# adapterSchematic.net
KiCad netlist of a schematic drawn in EAGLE
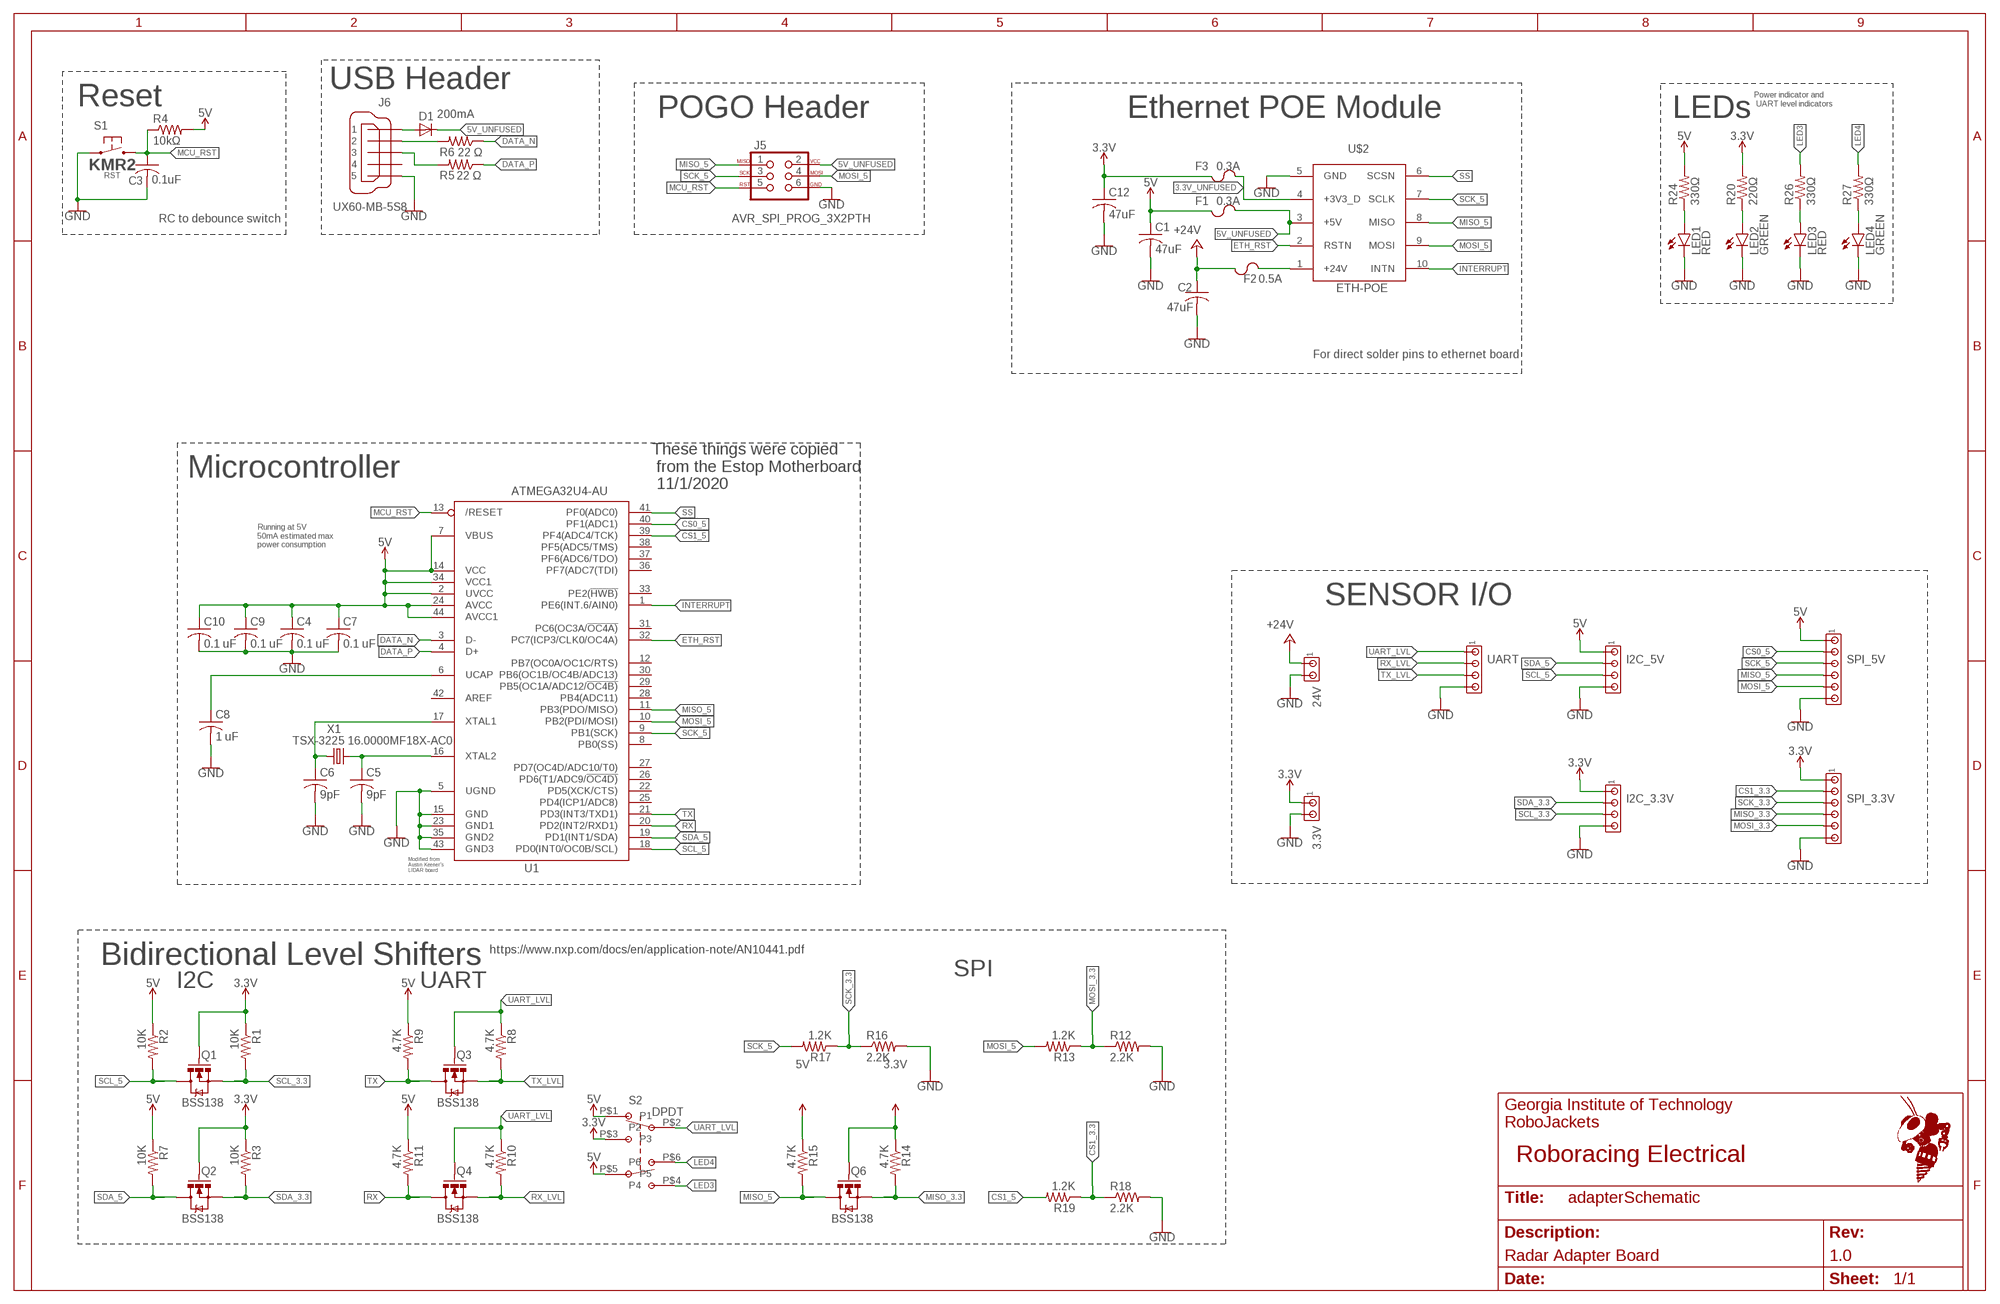
[diagram p0: schematic, sheet 1]

(export (version "E")
  (design (tool "Eeschema 10.0.6"))
  (components
    (comp (ref "3.3V")
      (value "MTA02-100")
      (footprint "eagle-import:10X02MTA")
      (libsource (lib "eagle-import") (part "MTA02-100"))
    )
    (comp (ref "24V")
      (value "MTA02-100")
      (footprint "eagle-import:10X02MTA")
      (libsource (lib "eagle-import") (part "MTA02-100"))
    )
    (comp (ref "C1")
      (value "47uF")
      (footprint "eagle-import:C1206")
      (libsource (lib "eagle-import") (part "C-USC1206"))
    )
    (comp (ref "C2")
      (value "47uF")
      (footprint "eagle-import:C1206")
      (libsource (lib "eagle-import") (part "C-USC1206"))
    )
    (comp (ref "C3")
      (value "0.1uF")
      (footprint "eagle-import:C0603")
      (libsource (lib "eagle-import") (part "C-USC0603"))
    )
    (comp (ref "C4")
      (value "0.1 uF")
      (footprint "eagle-import:C0603")
      (libsource (lib "eagle-import") (part "resistor_348_C-USC0603"))
    )
    (comp (ref "C5")
      (value "9pF")
      (footprint "eagle-import:C0603")
      (libsource (lib "eagle-import") (part "resistor_348_C-USC0603"))
    )
    (comp (ref "C6")
      (value "9pF")
      (footprint "eagle-import:C0603")
      (libsource (lib "eagle-import") (part "resistor_348_C-USC0603"))
    )
    (comp (ref "C7")
      (value "0.1 uF")
      (footprint "eagle-import:C0603")
      (libsource (lib "eagle-import") (part "resistor_348_C-USC0603"))
    )
    (comp (ref "C8")
      (value "1 uF")
      (footprint "eagle-import:C0603")
      (libsource (lib "eagle-import") (part "resistor_348_C-USC0603"))
    )
    (comp (ref "C9")
      (value "0.1 uF")
      (footprint "eagle-import:C0603")
      (libsource (lib "eagle-import") (part "resistor_348_C-USC0603"))
    )
    (comp (ref "C10")
      (value "0.1 uF")
      (footprint "eagle-import:C0603")
      (libsource (lib "eagle-import") (part "resistor_348_C-USC0603"))
    )
    (comp (ref "C12")
      (value "47uF")
      (footprint "eagle-import:C1206")
      (libsource (lib "eagle-import") (part "C-USC1206"))
    )
    (comp (ref "D1")
      (value "200mA")
      (footprint "eagle-import:SOD323-R")
      (libsource (lib "eagle-import") (part "DIODE-SOD323-R"))
    )
    (comp (ref "F1")
      (value "0.3A")
      (footprint "eagle-import:F1206")
      (libsource (lib "eagle-import") (part "CHIP_FUSE1206"))
    )
    (comp (ref "F2")
      (value "0.5A")
      (footprint "eagle-import:F1206")
      (libsource (lib "eagle-import") (part "CHIP_FUSE1206"))
    )
    (comp (ref "F3")
      (value "0.3A")
      (footprint "eagle-import:F1206")
      (libsource (lib "eagle-import") (part "CHIP_FUSE1206"))
    )
    (comp (ref "I2C_3.3V")
      (value "MTA04-100")
      (footprint "eagle-import:10X04MTA")
      (libsource (lib "eagle-import") (part "MTA04-100"))
    )
    (comp (ref "I2C_5V")
      (value "MTA04-100")
      (footprint "eagle-import:10X04MTA")
      (libsource (lib "eagle-import") (part "MTA04-100"))
    )
    (comp (ref "J5")
      (value "AVR_SPI_PROG_3X2PTH")
      (footprint "eagle-import:2X3")
      (libsource (lib "eagle-import") (part "AVR_SPI_PROG_3X2PTH"))
    )
    (comp (ref "J6")
      (value "UX60-MB-5S8")
      (footprint "eagle-import:UX60-MB-5S8")
      (libsource (lib "eagle-import") (part "UX60-MB-5S?8"))
    )
    (comp (ref "LED1")
      (value "RED")
      (footprint "eagle-import:CHIP-LED0603")
      (libsource (lib "eagle-import") (part "LEDCHIP-LED0603"))
    )
    (comp (ref "LED2")
      (value "GREEN")
      (footprint "eagle-import:CHIP-LED0603")
      (libsource (lib "eagle-import") (part "LEDCHIP-LED0603"))
    )
    (comp (ref "LED3")
      (value "RED")
      (footprint "eagle-import:CHIP-LED0603")
      (libsource (lib "eagle-import") (part "LEDCHIP-LED0603"))
    )
    (comp (ref "LED4")
      (value "GREEN")
      (footprint "eagle-import:CHIP-LED0603")
      (libsource (lib "eagle-import") (part "LEDCHIP-LED0603"))
    )
    (comp (ref "Q1")
      (value "BSS138")
      (footprint "eagle-import:SOT23-3")
      (libsource (lib "eagle-import") (part "MOSFET-NCHANNELSMD"))
    )
    (comp (ref "Q2")
      (value "BSS138")
      (footprint "eagle-import:SOT23-3")
      (libsource (lib "eagle-import") (part "MOSFET-NCHANNELSMD"))
    )
    (comp (ref "Q3")
      (value "BSS138")
      (footprint "eagle-import:SOT23-3")
      (libsource (lib "eagle-import") (part "MOSFET-NCHANNELSMD"))
    )
    (comp (ref "Q4")
      (value "BSS138")
      (footprint "eagle-import:SOT23-3")
      (libsource (lib "eagle-import") (part "MOSFET-NCHANNELSMD"))
    )
    (comp (ref "Q6")
      (value "BSS138")
      (footprint "eagle-import:SOT23-3")
      (libsource (lib "eagle-import") (part "MOSFET-NCHANNELSMD"))
    )
    (comp (ref "R1")
      (value "10K")
      (footprint "eagle-import:0603-RES")
      (libsource (lib "eagle-import") (part "RESISTOR0603-RES"))
    )
    (comp (ref "R2")
      (value "10K")
      (footprint "eagle-import:0603-RES")
      (libsource (lib "eagle-import") (part "RESISTOR0603-RES"))
    )
    (comp (ref "R3")
      (value "10K")
      (footprint "eagle-import:0603-RES")
      (libsource (lib "eagle-import") (part "RESISTOR0603-RES"))
    )
    (comp (ref "R4")
      (value "10kΩ")
      (footprint "eagle-import:R0603")
      (libsource (lib "eagle-import") (part "R-US_R0603"))
    )
    (comp (ref "R5")
      (value "22 Ω")
      (footprint "eagle-import:R0603")
      (libsource (lib "eagle-import") (part "R-US_R0603"))
    )
    (comp (ref "R6")
      (value "22 Ω")
      (footprint "eagle-import:R0603")
      (libsource (lib "eagle-import") (part "R-US_R0603"))
    )
    (comp (ref "R7")
      (value "10K")
      (footprint "eagle-import:0603-RES")
      (libsource (lib "eagle-import") (part "RESISTOR0603-RES"))
    )
    (comp (ref "R8")
      (value "4.7K")
      (footprint "eagle-import:0603-RES")
      (libsource (lib "eagle-import") (part "RESISTOR0603-RES"))
    )
    (comp (ref "R9")
      (value "4.7K")
      (footprint "eagle-import:0603-RES")
      (libsource (lib "eagle-import") (part "RESISTOR0603-RES"))
    )
    (comp (ref "R10")
      (value "4.7K")
      (footprint "eagle-import:0603-RES")
      (libsource (lib "eagle-import") (part "RESISTOR0603-RES"))
    )
    (comp (ref "R11")
      (value "4.7K")
      (footprint "eagle-import:0603-RES")
      (libsource (lib "eagle-import") (part "RESISTOR0603-RES"))
    )
    (comp (ref "R12")
      (value "2.2K")
      (footprint "eagle-import:0603-RES")
      (libsource (lib "eagle-import") (part "RESISTOR0603-RES"))
    )
    (comp (ref "R13")
      (value "1.2K")
      (footprint "eagle-import:0603-RES")
      (libsource (lib "eagle-import") (part "RESISTOR0603-RES"))
    )
    (comp (ref "R14")
      (value "4.7K")
      (footprint "eagle-import:0603-RES")
      (libsource (lib "eagle-import") (part "RESISTOR0603-RES"))
    )
    (comp (ref "R15")
      (value "4.7K")
      (footprint "eagle-import:0603-RES")
      (libsource (lib "eagle-import") (part "RESISTOR0603-RES"))
    )
    (comp (ref "R16")
      (value "2.2K")
      (footprint "eagle-import:0603-RES")
      (libsource (lib "eagle-import") (part "RESISTOR0603-RES"))
    )
    (comp (ref "R17")
      (value "1.2K")
      (footprint "eagle-import:0603-RES")
      (libsource (lib "eagle-import") (part "RESISTOR0603-RES"))
    )
    (comp (ref "R18")
      (value "2.2K")
      (footprint "eagle-import:0603-RES")
      (libsource (lib "eagle-import") (part "RESISTOR0603-RES"))
    )
    (comp (ref "R19")
      (value "1.2K")
      (footprint "eagle-import:0603-RES")
      (libsource (lib "eagle-import") (part "RESISTOR0603-RES"))
    )
    (comp (ref "R20")
      (value "220Ω")
      (footprint "eagle-import:R0603")
      (libsource (lib "eagle-import") (part "R-US_R0603"))
    )
    (comp (ref "R24")
      (value "330Ω")
      (footprint "eagle-import:R0603")
      (libsource (lib "eagle-import") (part "R-US_R0603"))
    )
    (comp (ref "R26")
      (value "330Ω")
      (footprint "eagle-import:R0603")
      (libsource (lib "eagle-import") (part "R-US_R0603"))
    )
    (comp (ref "R27")
      (value "330Ω")
      (footprint "eagle-import:R0603")
      (libsource (lib "eagle-import") (part "R-US_R0603"))
    )
    (comp (ref "S1")
      (value "KMR2")
      (footprint "eagle-import:KMR2")
      (fields (field (name "FUNCTION") "Reset") (field (name "FUNCTION_1") "RST"))
      (libsource (lib "eagle-import") (part "KMR2"))
    )
    (comp (ref "SPI_3.3V")
      (value "MTA06-100")
      (footprint "eagle-import:10X06MTA")
      (libsource (lib "eagle-import") (part "MTA06-100"))
    )
    (comp (ref "SPI_5V")
      (value "MTA06-100")
      (footprint "eagle-import:10X06MTA")
      (libsource (lib "eagle-import") (part "MTA06-100"))
    )
    (comp (ref "U$2")
      (value "ETH-POE")
      (footprint "eagle-import:HDRVR10W64P4000X254_2X5_1016X508X254B")
      (libsource (lib "eagle-import") (part "ETH-POE"))
    )
    (comp (ref "U$4")
      (value "DPDT_SLIDE_SWITCH")
      (footprint "eagle-import:DPDT_SLIDE_SWITCH")
      (libsource (lib "eagle-import") (part "DPDT_SLIDE_SWITCH"))
    )
    (comp (ref "U1")
      (value "ATMEGA32U4-AU")
      (footprint "eagle-import:TQFP44")
      (libsource (lib "eagle-import") (part "ATMEGA32U4-AU"))
    )
    (comp (ref "UART")
      (value "MTA04-100")
      (footprint "eagle-import:10X04MTA")
      (libsource (lib "eagle-import") (part "MTA04-100"))
    )
    (comp (ref "X1")
      (value "TSX-3225 16.0000MF18X-AC0")
      (footprint "eagle-import:XTAL-3.2X2.5")
      (libsource (lib "eagle-import") (part "XTAL-3.2X2.5"))
    )
  )
  (nets
    (net (code "1") (name "+24V") (class "Default")
      (node (ref "24V") (pin "1") (pinfunction "1_1") (pintype "passive"))
      (node (ref "C2") (pin "1") (pinfunction "1_1") (pintype "passive"))
      (node (ref "F2") (pin "1") (pinfunction "1_1") (pintype "bidirectional"))
    )
    (net (code "2") (name "3.3V") (class "Default")
      (node (ref "3.3V") (pin "1") (pinfunction "1_1") (pintype "passive"))
      (node (ref "C12") (pin "1") (pinfunction "1_1") (pintype "passive"))
      (node (ref "F3") (pin "1") (pinfunction "1_1") (pintype "bidirectional"))
      (node (ref "I2C_3.3V") (pin "1") (pinfunction "1_1") (pintype "passive"))
      (node (ref "Q1") (pin "1") (pinfunction "G_1") (pintype "passive"))
      (node (ref "Q2") (pin "1") (pinfunction "G_1") (pintype "passive"))
      (node (ref "Q6") (pin "1") (pinfunction "G_1") (pintype "passive"))
      (node (ref "R1") (pin "1") (pinfunction "1_1") (pintype "passive"))
      (node (ref "R14") (pin "1") (pinfunction "1_1") (pintype "passive"))
      (node (ref "R20") (pin "2") (pinfunction "2_2") (pintype "passive"))
      (node (ref "R3") (pin "1") (pinfunction "1_1") (pintype "passive"))
      (node (ref "SPI_3.3V") (pin "1") (pinfunction "1_1") (pintype "passive"))
      (node (ref "U$4") (pin "P$3") (pinfunction "P3_P$3") (pintype "bidirectional"))
    )
    (net (code "3") (name "3.3V_UNFUSED") (class "Default")
      (node (ref "F3") (pin "2") (pinfunction "2_2") (pintype "bidirectional"))
      (node (ref "U$2") (pin "4") (pinfunction "+3V3_D_4") (pintype "bidirectional"))
    )
    (net (code "4") (name "5V") (class "Default")
      (node (ref "C1") (pin "1") (pinfunction "1_1") (pintype "passive"))
      (node (ref "C10") (pin "1") (pinfunction "1_1") (pintype "passive"))
      (node (ref "C4") (pin "1") (pinfunction "1_1") (pintype "passive"))
      (node (ref "C7") (pin "1") (pinfunction "1_1") (pintype "passive"))
      (node (ref "C9") (pin "1") (pinfunction "1_1") (pintype "passive"))
      (node (ref "F1") (pin "1") (pinfunction "1_1") (pintype "bidirectional"))
      (node (ref "I2C_5V") (pin "1") (pinfunction "1_1") (pintype "passive"))
      (node (ref "R11") (pin "1") (pinfunction "1_1") (pintype "passive"))
      (node (ref "R15") (pin "1") (pinfunction "1_1") (pintype "passive"))
      (node (ref "R2") (pin "1") (pinfunction "1_1") (pintype "passive"))
      (node (ref "R24") (pin "2") (pinfunction "2_2") (pintype "passive"))
      (node (ref "R4") (pin "2") (pinfunction "2_2") (pintype "passive"))
      (node (ref "R7") (pin "1") (pinfunction "1_1") (pintype "passive"))
      (node (ref "R9") (pin "1") (pinfunction "1_1") (pintype "passive"))
      (node (ref "SPI_5V") (pin "1") (pinfunction "1_1") (pintype "passive"))
      (node (ref "U$4") (pin "P$1") (pinfunction "P1_P$1") (pintype "bidirectional"))
      (node (ref "U$4") (pin "P$5") (pinfunction "P5_P$5") (pintype "bidirectional"))
      (node (ref "U1") (pin "14") (pinfunction "VCC_14") (pintype "bidirectional"))
      (node (ref "U1") (pin "2") (pinfunction "UVCC_2") (pintype "bidirectional"))
      (node (ref "U1") (pin "24") (pinfunction "AVCC_24") (pintype "bidirectional"))
      (node (ref "U1") (pin "34") (pinfunction "VCC1_34") (pintype "bidirectional"))
      (node (ref "U1") (pin "44") (pinfunction "AVCC1_44") (pintype "bidirectional"))
      (node (ref "U1") (pin "7") (pinfunction "VBUS_7") (pintype "bidirectional"))
    )
    (net (code "5") (name "5V_UNFUSED") (class "Default")
      (node (ref "D1") (pin "C") (pinfunction "C_C") (pintype "passive"))
      (node (ref "F1") (pin "2") (pinfunction "2_2") (pintype "bidirectional"))
      (node (ref "J5") (pin "2") (pinfunction "2_2") (pintype "passive"))
      (node (ref "U$2") (pin "3") (pinfunction "+5V_3") (pintype "bidirectional"))
    )
    (net (code "6") (name "CS0_5") (class "Default")
      (node (ref "SPI_5V") (pin "2") (pinfunction "2_2") (pintype "passive"))
      (node (ref "U1") (pin "40") (pinfunction "PF1(ADC1)_40") (pintype "bidirectional"))
    )
    (net (code "7") (name "CS1_3.3") (class "Default")
      (node (ref "R18") (pin "1") (pinfunction "1_1") (pintype "passive"))
      (node (ref "R19") (pin "1") (pinfunction "1_1") (pintype "passive"))
      (node (ref "SPI_3.3V") (pin "2") (pinfunction "2_2") (pintype "passive"))
    )
    (net (code "8") (name "CS1_5") (class "Default")
      (node (ref "R19") (pin "2") (pinfunction "2_2") (pintype "passive"))
      (node (ref "U1") (pin "39") (pinfunction "PF4(ADC4/TCK)_39") (pintype "bidirectional"))
    )
    (net (code "9") (name "DATA_N") (class "Default")
      (node (ref "R6") (pin "1") (pinfunction "1_1") (pintype "passive"))
      (node (ref "U1") (pin "3") (pinfunction "D-_3") (pintype "bidirectional"))
    )
    (net (code "10") (name "DATA_P") (class "Default")
      (node (ref "R5") (pin "1") (pinfunction "1_1") (pintype "passive"))
      (node (ref "U1") (pin "4") (pinfunction "D+_4") (pintype "bidirectional"))
    )
    (net (code "11") (name "ETH_RST") (class "Default")
      (node (ref "U$2") (pin "2") (pinfunction "RSTN_2") (pintype "bidirectional"))
      (node (ref "U1") (pin "32") (pinfunction "PC7(ICP3/CLK0/OC4A)_32") (pintype "bidirectional"))
    )
    (net (code "12") (name "GND") (class "Default")
      (node (ref "24V") (pin "2") (pinfunction "2_2") (pintype "passive"))
      (node (ref "3.3V") (pin "2") (pinfunction "2_2") (pintype "passive"))
      (node (ref "C1") (pin "2") (pinfunction "2_2") (pintype "passive"))
      (node (ref "C10") (pin "2") (pinfunction "2_2") (pintype "passive"))
      (node (ref "C12") (pin "2") (pinfunction "2_2") (pintype "passive"))
      (node (ref "C2") (pin "2") (pinfunction "2_2") (pintype "passive"))
      (node (ref "C3") (pin "2") (pinfunction "2_2") (pintype "passive"))
      (node (ref "C4") (pin "2") (pinfunction "2_2") (pintype "passive"))
      (node (ref "C5") (pin "2") (pinfunction "2_2") (pintype "passive"))
      (node (ref "C6") (pin "2") (pinfunction "2_2") (pintype "passive"))
      (node (ref "C7") (pin "2") (pinfunction "2_2") (pintype "passive"))
      (node (ref "C8") (pin "2") (pinfunction "2_2") (pintype "passive"))
      (node (ref "C9") (pin "2") (pinfunction "2_2") (pintype "passive"))
      (node (ref "I2C_3.3V") (pin "4") (pinfunction "4_4") (pintype "passive"))
      (node (ref "I2C_5V") (pin "4") (pinfunction "4_4") (pintype "passive"))
      (node (ref "J5") (pin "6") (pinfunction "6_6") (pintype "passive"))
      (node (ref "J6") (pin "5") (pinfunction "5_5") (pintype "passive"))
      (node (ref "LED1") (pin "C") (pinfunction "C_C") (pintype "passive"))
      (node (ref "LED2") (pin "C") (pinfunction "C_C") (pintype "passive"))
      (node (ref "LED3") (pin "C") (pinfunction "C_C") (pintype "passive"))
      (node (ref "LED4") (pin "C") (pinfunction "C_C") (pintype "passive"))
      (node (ref "R12") (pin "2") (pinfunction "2_2") (pintype "passive"))
      (node (ref "R16") (pin "2") (pinfunction "2_2") (pintype "passive"))
      (node (ref "R18") (pin "2") (pinfunction "2_2") (pintype "passive"))
      (node (ref "S1") (pin "1.1") (pinfunction "1_1.1") (pintype "passive"))
      (node (ref "S1") (pin "1.2") (pinfunction "1_1.2") (pintype "passive"))
      (node (ref "SPI_3.3V") (pin "6") (pinfunction "6_6") (pintype "passive"))
      (node (ref "SPI_5V") (pin "6") (pinfunction "6_6") (pintype "passive"))
      (node (ref "U$2") (pin "5") (pinfunction "GND_5") (pintype "bidirectional"))
      (node (ref "U1") (pin "15") (pinfunction "GND_15") (pintype "bidirectional"))
      (node (ref "U1") (pin "23") (pinfunction "GND1_23") (pintype "bidirectional"))
      (node (ref "U1") (pin "35") (pinfunction "GND2_35") (pintype "bidirectional"))
      (node (ref "U1") (pin "43") (pinfunction "GND3_43") (pintype "bidirectional"))
      (node (ref "U1") (pin "5") (pinfunction "UGND_5") (pintype "bidirectional"))
      (node (ref "UART") (pin "4") (pinfunction "4_4") (pintype "passive"))
    )
    (net (code "13") (name "INTERRUPT") (class "Default")
      (node (ref "U$2") (pin "10") (pinfunction "INTN_10") (pintype "bidirectional"))
      (node (ref "U1") (pin "1") (pinfunction "PE6(INT.6/AIN0)_1") (pintype "bidirectional"))
    )
    (net (code "14") (name "LED3") (class "Default")
      (node (ref "R26") (pin "2") (pinfunction "2_2") (pintype "passive"))
      (node (ref "U$4") (pin "P$4") (pinfunction "P4_P$4") (pintype "bidirectional"))
    )
    (net (code "15") (name "LED4") (class "Default")
      (node (ref "R27") (pin "2") (pinfunction "2_2") (pintype "passive"))
      (node (ref "U$4") (pin "P$6") (pinfunction "P6_P$6") (pintype "bidirectional"))
    )
    (net (code "16") (name "MCU_RST") (class "Default")
      (node (ref "C3") (pin "1") (pinfunction "1_1") (pintype "passive"))
      (node (ref "J5") (pin "5") (pinfunction "5_5") (pintype "passive"))
      (node (ref "R4") (pin "1") (pinfunction "1_1") (pintype "passive"))
      (node (ref "S1") (pin "2.1") (pinfunction "2_2.1") (pintype "passive"))
      (node (ref "S1") (pin "2.2") (pinfunction "2_2.2") (pintype "passive"))
      (node (ref "U1") (pin "13") (pinfunction "/RESET_13") (pintype "bidirectional"))
    )
    (net (code "17") (name "MISO_3.3") (class "Default")
      (node (ref "Q6") (pin "2") (pinfunction "S_2") (pintype "passive"))
      (node (ref "R14") (pin "2") (pinfunction "2_2") (pintype "passive"))
      (node (ref "SPI_3.3V") (pin "4") (pinfunction "4_4") (pintype "passive"))
    )
    (net (code "18") (name "MISO_5") (class "Default")
      (node (ref "J5") (pin "1") (pinfunction "1_1") (pintype "passive"))
      (node (ref "Q6") (pin "3") (pinfunction "D_3") (pintype "passive"))
      (node (ref "R15") (pin "2") (pinfunction "2_2") (pintype "passive"))
      (node (ref "SPI_5V") (pin "4") (pinfunction "4_4") (pintype "passive"))
      (node (ref "U$2") (pin "8") (pinfunction "MISO_8") (pintype "bidirectional"))
      (node (ref "U1") (pin "11") (pinfunction "PB3(PDO/MISO)_11") (pintype "bidirectional"))
    )
    (net (code "19") (name "MOSI_3.3") (class "Default")
      (node (ref "R12") (pin "1") (pinfunction "1_1") (pintype "passive"))
      (node (ref "R13") (pin "1") (pinfunction "1_1") (pintype "passive"))
      (node (ref "SPI_3.3V") (pin "5") (pinfunction "5_5") (pintype "passive"))
    )
    (net (code "20") (name "MOSI_5") (class "Default")
      (node (ref "J5") (pin "4") (pinfunction "4_4") (pintype "passive"))
      (node (ref "R13") (pin "2") (pinfunction "2_2") (pintype "passive"))
      (node (ref "SPI_5V") (pin "5") (pinfunction "5_5") (pintype "passive"))
      (node (ref "U$2") (pin "9") (pinfunction "MOSI_9") (pintype "bidirectional"))
      (node (ref "U1") (pin "10") (pinfunction "PB2(PDI/MOSI)_10") (pintype "bidirectional"))
    )
    (net (code "21") (name "Net-(D1-PadA)") (class "Default")
      (node (ref "D1") (pin "A") (pinfunction "A_A") (pintype "passive"))
      (node (ref "J6") (pin "1") (pinfunction "1_1") (pintype "passive"))
    )
    (net (code "22") (name "Net-(J6-Pad2)") (class "Default")
      (node (ref "J6") (pin "2") (pinfunction "2_2") (pintype "passive"))
      (node (ref "R6") (pin "2") (pinfunction "2_2") (pintype "passive"))
    )
    (net (code "23") (name "Net-(J6-Pad3)") (class "Default")
      (node (ref "J6") (pin "3") (pinfunction "3_3") (pintype "passive"))
      (node (ref "R5") (pin "2") (pinfunction "2_2") (pintype "passive"))
    )
    (net (code "24") (name "Net-(LED1-PadA)") (class "Default")
      (node (ref "LED1") (pin "A") (pinfunction "A_A") (pintype "passive"))
      (node (ref "R24") (pin "1") (pinfunction "1_1") (pintype "passive"))
    )
    (net (code "25") (name "Net-(LED2-PadA)") (class "Default")
      (node (ref "LED2") (pin "A") (pinfunction "A_A") (pintype "passive"))
      (node (ref "R20") (pin "1") (pinfunction "1_1") (pintype "passive"))
    )
    (net (code "26") (name "Net-(LED3-PadA)") (class "Default")
      (node (ref "LED3") (pin "A") (pinfunction "A_A") (pintype "passive"))
      (node (ref "R26") (pin "1") (pinfunction "1_1") (pintype "passive"))
    )
    (net (code "27") (name "Net-(LED4-PadA)") (class "Default")
      (node (ref "LED4") (pin "A") (pinfunction "A_A") (pintype "passive"))
      (node (ref "R27") (pin "1") (pinfunction "1_1") (pintype "passive"))
    )
    (net (code "28") (name "Net-(U$2-+24V)") (class "Default")
      (node (ref "F2") (pin "2") (pinfunction "2_2") (pintype "bidirectional"))
      (node (ref "U$2") (pin "1") (pinfunction "+24V_1") (pintype "bidirectional"))
    )
    (net (code "29") (name "Net-(U1-UCAP)") (class "Default")
      (node (ref "C8") (pin "1") (pinfunction "1_1") (pintype "passive"))
      (node (ref "U1") (pin "6") (pinfunction "UCAP_6") (pintype "bidirectional"))
    )
    (net (code "30") (name "Net-(U1-XTAL1)") (class "Default")
      (node (ref "C6") (pin "1") (pinfunction "1_1") (pintype "passive"))
      (node (ref "U1") (pin "17") (pinfunction "XTAL1_17") (pintype "bidirectional"))
      (node (ref "X1") (pin "1") (pinfunction "1_1") (pintype "passive"))
    )
    (net (code "31") (name "Net-(U1-XTAL2)") (class "Default")
      (node (ref "C5") (pin "1") (pinfunction "1_1") (pintype "passive"))
      (node (ref "U1") (pin "16") (pinfunction "XTAL2_16") (pintype "bidirectional"))
      (node (ref "X1") (pin "3") (pinfunction "2_3") (pintype "passive"))
    )
    (net (code "32") (name "RX") (class "Default")
      (node (ref "Q4") (pin "3") (pinfunction "D_3") (pintype "passive"))
      (node (ref "R11") (pin "2") (pinfunction "2_2") (pintype "passive"))
      (node (ref "U1") (pin "20") (pinfunction "PD2(INT2/RXD1)_20") (pintype "bidirectional"))
    )
    (net (code "33") (name "RX_LVL") (class "Default")
      (node (ref "Q4") (pin "2") (pinfunction "S_2") (pintype "passive"))
      (node (ref "R10") (pin "2") (pinfunction "2_2") (pintype "passive"))
      (node (ref "UART") (pin "2") (pinfunction "2_2") (pintype "passive"))
    )
    (net (code "34") (name "SCK_3.3") (class "Default")
      (node (ref "R16") (pin "1") (pinfunction "1_1") (pintype "passive"))
      (node (ref "R17") (pin "1") (pinfunction "1_1") (pintype "passive"))
      (node (ref "SPI_3.3V") (pin "3") (pinfunction "3_3") (pintype "passive"))
    )
    (net (code "35") (name "SCK_5") (class "Default")
      (node (ref "J5") (pin "3") (pinfunction "3_3") (pintype "passive"))
      (node (ref "R17") (pin "2") (pinfunction "2_2") (pintype "passive"))
      (node (ref "SPI_5V") (pin "3") (pinfunction "3_3") (pintype "passive"))
      (node (ref "U$2") (pin "7") (pinfunction "SCLK_7") (pintype "bidirectional"))
      (node (ref "U1") (pin "9") (pinfunction "PB1(SCK)_9") (pintype "bidirectional"))
    )
    (net (code "36") (name "SCL_3.3") (class "Default")
      (node (ref "I2C_3.3V") (pin "3") (pinfunction "3_3") (pintype "passive"))
      (node (ref "Q1") (pin "2") (pinfunction "S_2") (pintype "passive"))
      (node (ref "R1") (pin "2") (pinfunction "2_2") (pintype "passive"))
    )
    (net (code "37") (name "SCL_5") (class "Default")
      (node (ref "I2C_5V") (pin "3") (pinfunction "3_3") (pintype "passive"))
      (node (ref "Q1") (pin "3") (pinfunction "D_3") (pintype "passive"))
      (node (ref "R2") (pin "2") (pinfunction "2_2") (pintype "passive"))
      (node (ref "U1") (pin "18") (pinfunction "PD0(INT0/OC0B/SCL)_18") (pintype "bidirectional"))
    )
    (net (code "38") (name "SDA_3.3") (class "Default")
      (node (ref "I2C_3.3V") (pin "2") (pinfunction "2_2") (pintype "passive"))
      (node (ref "Q2") (pin "2") (pinfunction "S_2") (pintype "passive"))
      (node (ref "R3") (pin "2") (pinfunction "2_2") (pintype "passive"))
    )
    (net (code "39") (name "SDA_5") (class "Default")
      (node (ref "I2C_5V") (pin "2") (pinfunction "2_2") (pintype "passive"))
      (node (ref "Q2") (pin "3") (pinfunction "D_3") (pintype "passive"))
      (node (ref "R7") (pin "2") (pinfunction "2_2") (pintype "passive"))
      (node (ref "U1") (pin "19") (pinfunction "PD1(INT1/SDA)_19") (pintype "bidirectional"))
    )
    (net (code "40") (name "SS") (class "Default")
      (node (ref "U$2") (pin "6") (pinfunction "SCSN_6") (pintype "bidirectional"))
      (node (ref "U1") (pin "41") (pinfunction "PF0(ADC0)_41") (pintype "bidirectional"))
    )
    (net (code "41") (name "TX") (class "Default")
      (node (ref "Q3") (pin "3") (pinfunction "D_3") (pintype "passive"))
      (node (ref "R9") (pin "2") (pinfunction "2_2") (pintype "passive"))
      (node (ref "U1") (pin "21") (pinfunction "PD3(INT3/TXD1)_21") (pintype "bidirectional"))
    )
    (net (code "42") (name "TX_LVL") (class "Default")
      (node (ref "Q3") (pin "2") (pinfunction "S_2") (pintype "passive"))
      (node (ref "R8") (pin "2") (pinfunction "2_2") (pintype "passive"))
      (node (ref "UART") (pin "3") (pinfunction "3_3") (pintype "passive"))
    )
    (net (code "43") (name "UART_LVL") (class "Default")
      (node (ref "Q3") (pin "1") (pinfunction "G_1") (pintype "passive"))
      (node (ref "Q4") (pin "1") (pinfunction "G_1") (pintype "passive"))
      (node (ref "R10") (pin "1") (pinfunction "1_1") (pintype "passive"))
      (node (ref "R8") (pin "1") (pinfunction "1_1") (pintype "passive"))
      (node (ref "U$4") (pin "P$2") (pinfunction "P2_P$2") (pintype "bidirectional"))
      (node (ref "UART") (pin "1") (pinfunction "1_1") (pintype "passive"))
    )
    (net (code "44") (name "unconnected-(J6-Pad4)") (class "Default")
      (node (ref "J6") (pin "4") (pinfunction "4_4") (pintype "passive"))
    )
    (net (code "45") (name "unconnected-(U1-AREF-Pad42)") (class "Default")
      (node (ref "U1") (pin "42") (pinfunction "AREF_42") (pintype "bidirectional"))
    )
    (net (code "46") (name "unconnected-(U1-PB0(SS)-Pad8)") (class "Default")
      (node (ref "U1") (pin "8") (pinfunction "PB0(SS)_8") (pintype "bidirectional"))
    )
    (net (code "47") (name "unconnected-(U1-PB4(ADC11)-Pad28)") (class "Default")
      (node (ref "U1") (pin "28") (pinfunction "PB4(ADC11)_28") (pintype "bidirectional"))
    )
    (net (code "48") (name "unconnected-(U1-PB5(OC1A{slash}ADC12{slash}~{OC4B})-Pad29)") (class "Default")
      (node (ref "U1") (pin "29") (pinfunction "PB5(OC1A/ADC12/~{OC4B})_29") (pintype "bidirectional"))
    )
    (net (code "49") (name "unconnected-(U1-PB6(OC1B{slash}OC4B{slash}ADC13)-Pad30)") (class "Default")
      (node (ref "U1") (pin "30") (pinfunction "PB6(OC1B/OC4B/ADC13)_30") (pintype "bidirectional"))
    )
    (net (code "50") (name "unconnected-(U1-PB7(OC0A{slash}OC1C{slash}RTS)-Pad12)") (class "Default")
      (node (ref "U1") (pin "12") (pinfunction "PB7(OC0A/OC1C/RTS)_12") (pintype "bidirectional"))
    )
    (net (code "51") (name "unconnected-(U1-PC6(OC3A{slash}~{OC4A})-Pad31)") (class "Default")
      (node (ref "U1") (pin "31") (pinfunction "PC6(OC3A/~{OC4A})_31") (pintype "bidirectional"))
    )
    (net (code "52") (name "unconnected-(U1-PD4(ICP1{slash}ADC8)-Pad25)") (class "Default")
      (node (ref "U1") (pin "25") (pinfunction "PD4(ICP1/ADC8)_25") (pintype "bidirectional"))
    )
    (net (code "53") (name "unconnected-(U1-PD5(XCK{slash}CTS)-Pad22)") (class "Default")
      (node (ref "U1") (pin "22") (pinfunction "PD5(XCK/CTS)_22") (pintype "bidirectional"))
    )
    (net (code "54") (name "unconnected-(U1-PD6(T1{slash}ADC9{slash}~{OC4D})-Pad26)") (class "Default")
      (node (ref "U1") (pin "26") (pinfunction "PD6(T1/ADC9/~{OC4D})_26") (pintype "bidirectional"))
    )
    (net (code "55") (name "unconnected-(U1-PD7(OC4D{slash}ADC10{slash}T0)-Pad27)") (class "Default")
      (node (ref "U1") (pin "27") (pinfunction "PD7(OC4D/ADC10/T0)_27") (pintype "bidirectional"))
    )
    (net (code "56") (name "unconnected-(U1-PE2(~{HWB})-Pad33)") (class "Default")
      (node (ref "U1") (pin "33") (pinfunction "PE2(~{HWB})_33") (pintype "bidirectional"))
    )
    (net (code "57") (name "unconnected-(U1-PF5(ADC5{slash}TMS)-Pad38)") (class "Default")
      (node (ref "U1") (pin "38") (pinfunction "PF5(ADC5/TMS)_38") (pintype "bidirectional"))
    )
    (net (code "58") (name "unconnected-(U1-PF6(ADC6{slash}TDO)-Pad37)") (class "Default")
      (node (ref "U1") (pin "37") (pinfunction "PF6(ADC6/TDO)_37") (pintype "bidirectional"))
    )
    (net (code "59") (name "unconnected-(U1-PF7(ADC7(TDI)-Pad36)") (class "Default")
      (node (ref "U1") (pin "36") (pinfunction "PF7(ADC7(TDI)_36") (pintype "bidirectional"))
    )
  )
)
